# schematic.net
KiCad netlist of a schematic drawn in EasyEDA
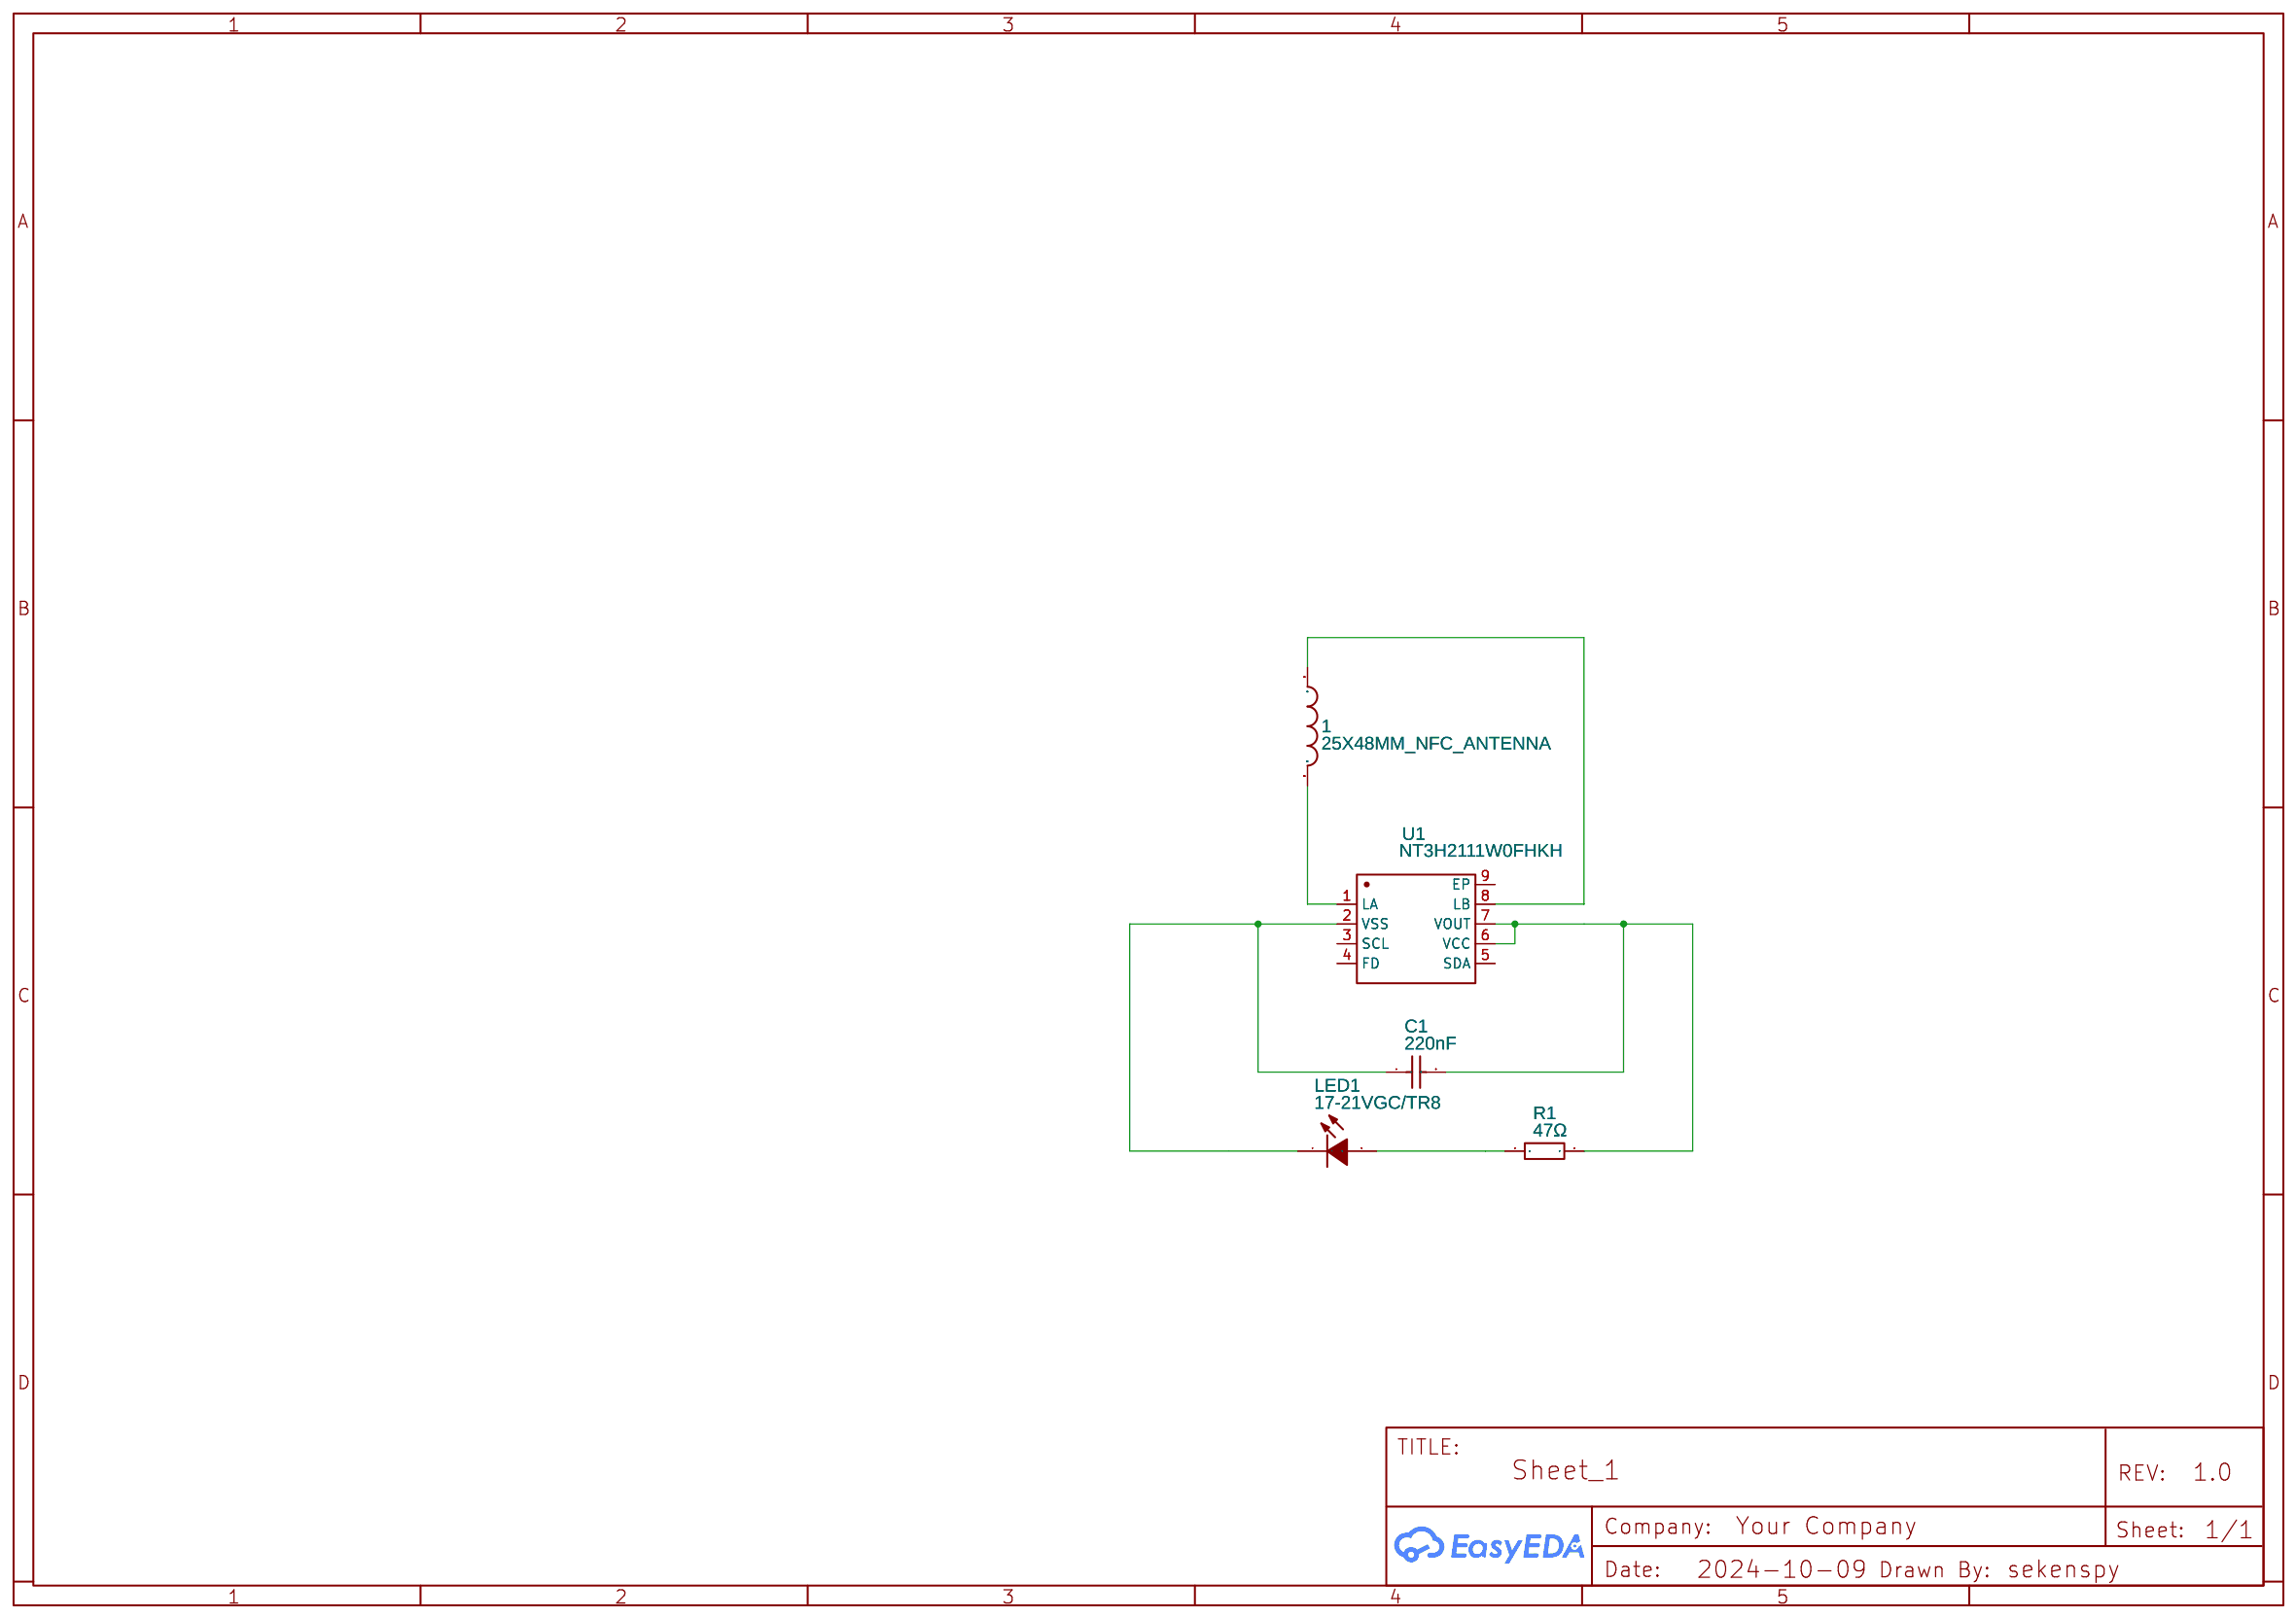
[diagram p0: schematic sheet]

(export (version "E")
  (design (tool "Eeschema 10.0.6"))
  (components
    (comp (ref "1") (value "25X48MM_NFC_ANTENNA") (libsource (lib "") (part "25X48MM_NFC_ANTENNA")))
    (comp (ref "C1")
      (value "220nF")
      (fields (field (name "Manufacturer Part") "CL10B224KA8NNNC") (field (name "Manufacturer") "SAMSUNG"))
      (libsource (lib "") (part "C21120"))
    )
    (comp (ref "LED1")
      (value "17-21VGC/TR8")
      (fields (field (name "Manufacturer") "EVERLIGHT(亿光)"))
      (libsource (lib "") (part "17-21VGC/TR8"))
    )
    (comp (ref "R1")
      (value "47Ω")
      (fields
        (field (name "Manufacturer Part") "0603WAF470JT5E")
        (field (name "Manufacturer") "UNI-ROYAL(厚声)")
      )
      (libsource (lib "") (part "0603WAF470JT5E"))
    )
    (comp (ref "U1")
      (value "NT3H2111W0FHKH")
      (fields (field (name "Manufacturer") "NXP(恩智浦)"))
      (libsource (lib "") (part "NT3H2111W0FHKH"))
    )
  )
  (nets
    (net (code "1") (name "Net-(LED1-+)") (class "Default")
      (node (ref "LED1") (pin "2") (pinfunction "+_2") (pintype "unspecified"))
      (node (ref "R1") (pin "1") (pinfunction "1_1") (pintype "unspecified"))
    )
    (net (code "2") (name "Net-(LED1--)") (class "Default")
      (node (ref "C1") (pin "1") (pinfunction "1_1") (pintype "input"))
      (node (ref "LED1") (pin "1") (pinfunction "-_1") (pintype "unspecified"))
      (node (ref "U1") (pin "2") (pinfunction "VSS_2") (pintype "unspecified"))
    )
    (net (code "3") (name "Net-(U1-LA)") (class "Default")
      (node (ref "1") (pin "P$2") (pinfunction "P$2_P$2") (pintype "bidirectional"))
      (node (ref "U1") (pin "1") (pinfunction "LA_1") (pintype "unspecified"))
    )
    (net (code "4") (name "Net-(U1-LB)") (class "Default")
      (node (ref "1") (pin "P$1") (pinfunction "P$1_P$1") (pintype "bidirectional"))
      (node (ref "U1") (pin "8") (pinfunction "LB_8") (pintype "unspecified"))
    )
    (net (code "5") (name "Net-(U1-VCC)") (class "Default")
      (node (ref "C1") (pin "2") (pinfunction "2_2") (pintype "input"))
      (node (ref "R1") (pin "2") (pinfunction "2_2") (pintype "unspecified"))
      (node (ref "U1") (pin "6") (pinfunction "VCC_6") (pintype "unspecified"))
      (node (ref "U1") (pin "7") (pinfunction "VOUT_7") (pintype "unspecified"))
    )
    (net (code "6") (name "unconnected-(U1-EP-Pad9)") (class "Default")
      (node (ref "U1") (pin "9") (pinfunction "EP_9") (pintype "unspecified"))
    )
    (net (code "7") (name "unconnected-(U1-FD-Pad4)") (class "Default")
      (node (ref "U1") (pin "4") (pinfunction "FD_4") (pintype "unspecified"))
    )
    (net (code "8") (name "unconnected-(U1-SCL-Pad3)") (class "Default")
      (node (ref "U1") (pin "3") (pinfunction "SCL_3") (pintype "unspecified"))
    )
    (net (code "9") (name "unconnected-(U1-SDA-Pad5)") (class "Default")
      (node (ref "U1") (pin "5") (pinfunction "SDA_5") (pintype "unspecified"))
    )
  )
)
